# LCD-Micro-PC.net
KiCad netlist of a schematic drawn in EAGLE
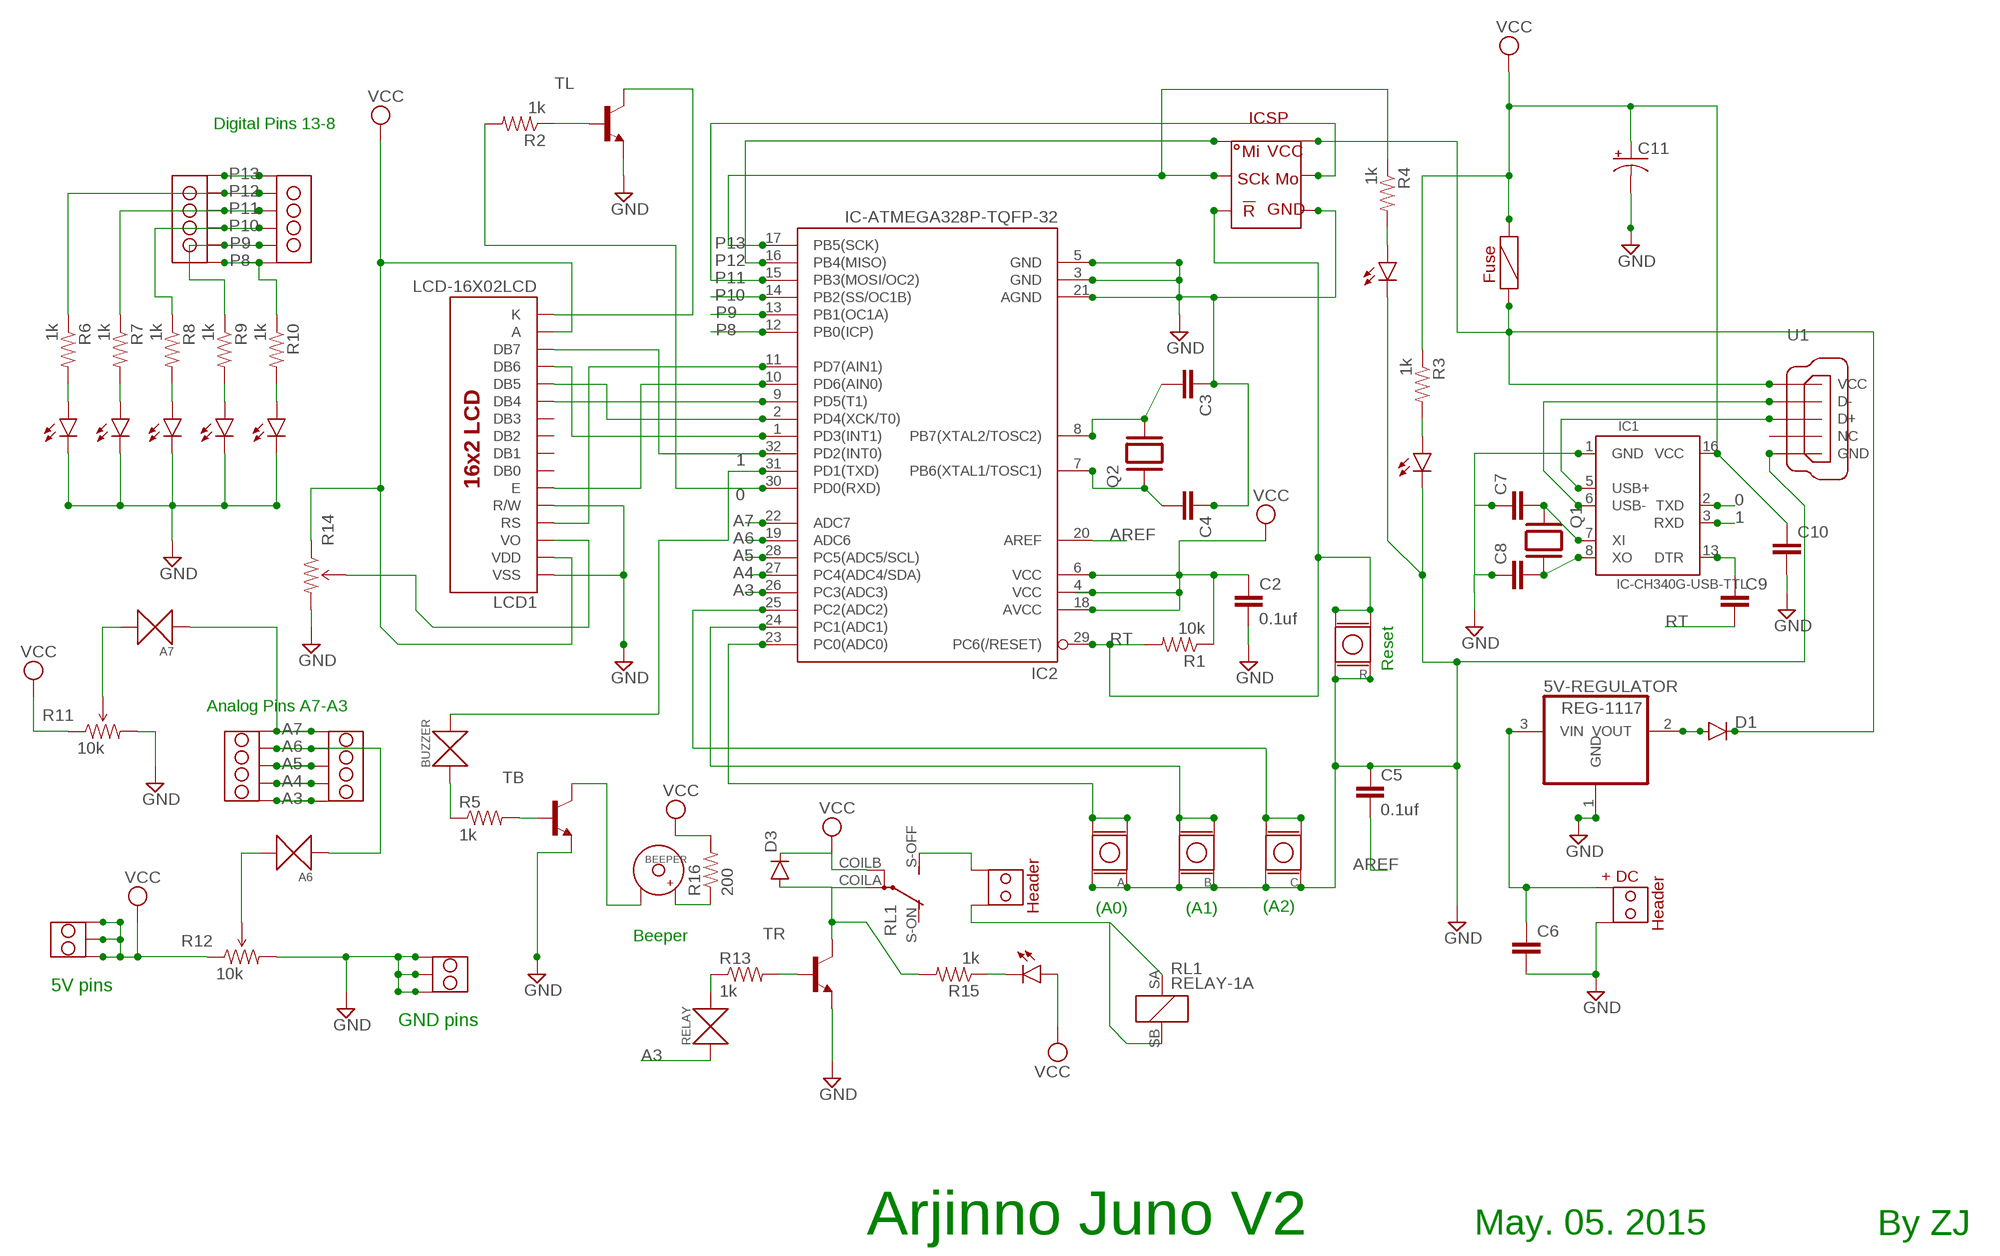
[diagram p0: schematic, sheet 1]

(export (version "E")
  (design (tool "Eeschema 10.0.6"))
  (components
    (comp (ref "5V-REGULATOR")
      (value "REG-1117")
      (footprint "eagle-import:SOT-223@1")
      (fields (field (name "MPN") "REG1117"))
      (libsource (lib "eagle-import") (part "REG-1117"))
    )
    (comp (ref "A")
      (value "BUTTON-6X6")
      (footprint "eagle-import:BUT-6X6")
      (libsource (lib "eagle-import") (part "BUTTON-6X6"))
    )
    (comp (ref "A6")
      (value "TRACE-0.6MM")
      (footprint "eagle-import:TRACE")
      (libsource (lib "eagle-import") (part "TRACE-0.6MM"))
    )
    (comp (ref "A7")
      (value "TRACE-0.6MM")
      (footprint "eagle-import:TRACE")
      (libsource (lib "eagle-import") (part "TRACE-0.6MM"))
    )
    (comp (ref "B")
      (value "BUTTON-6X6")
      (footprint "eagle-import:BUT-6X6")
      (libsource (lib "eagle-import") (part "BUTTON-6X6"))
    )
    (comp (ref "BEEPER")
      (value "BUZZER-12MM")
      (footprint "eagle-import:BUZ-12MM")
      (libsource (lib "eagle-import") (part "BUZZER-12MM"))
    )
    (comp (ref "BUZZER")
      (value "TRACE-0.6MM")
      (footprint "eagle-import:TRACE")
      (libsource (lib "eagle-import") (part "TRACE-0.6MM"))
    )
    (comp (ref "C")
      (value "BUTTON-6X6")
      (footprint "eagle-import:BUT-6X6")
      (libsource (lib "eagle-import") (part "BUTTON-6X6"))
    )
    (comp (ref "C2")
      (value "0.1uf")
      (footprint "eagle-import:0805")
      (libsource (lib "eagle-import") (part "CAP-0805"))
    )
    (comp (ref "C3")
      (value "CAP-0805")
      (footprint "eagle-import:0805")
      (libsource (lib "eagle-import") (part "CAP-0805"))
    )
    (comp (ref "C4")
      (value "CAP-0805")
      (footprint "eagle-import:0805")
      (libsource (lib "eagle-import") (part "CAP-0805"))
    )
    (comp (ref "C5")
      (value "0.1uf")
      (footprint "eagle-import:0805")
      (libsource (lib "eagle-import") (part "CAP-0805"))
    )
    (comp (ref "C6")
      (value "CAP-0805")
      (footprint "eagle-import:0805")
      (libsource (lib "eagle-import") (part "CAP-0805"))
    )
    (comp (ref "C7")
      (value "CAP-SMD-0805")
      (footprint "eagle-import:0805")
      (libsource (lib "eagle-import") (part "CAP-SMD-0805"))
    )
    (comp (ref "C8")
      (value "CAP-SMD-0805")
      (footprint "eagle-import:0805")
      (libsource (lib "eagle-import") (part "CAP-SMD-0805"))
    )
    (comp (ref "C9")
      (value "CAP-SMD-0805")
      (footprint "eagle-import:0805")
      (libsource (lib "eagle-import") (part "CAP-SMD-0805"))
    )
    (comp (ref "C10")
      (value "CAP-SMD-0805")
      (footprint "eagle-import:0805")
      (libsource (lib "eagle-import") (part "CAP-SMD-0805"))
    )
    (comp (ref "C11")
      (value "CAP-POL-6MM-SMD")
      (footprint "eagle-import:CAP-POL-6.3X7.7MM")
      (libsource (lib "eagle-import") (part "CAP-POL-6MM-SMD"))
    )
    (comp (ref "D1")
      (value "DIODE-SMA-4MM")
      (footprint "eagle-import:DIODE-SMA")
      (libsource (lib "eagle-import") (part "DIODE-SMA-4MM"))
    )
    (comp (ref "D3")
      (value "DIODE-SOD-1206")
      (footprint "eagle-import:SOD-1206")
      (libsource (lib "eagle-import") (part "DIODE-SOD-1206"))
    )
    (comp (ref "FUSE")
      (value "FUSE")
      (footprint "eagle-import:0805")
      (libsource (lib "eagle-import") (part "FUSE"))
    )
    (comp (ref "GND")
      (value "HEADER-3P")
      (footprint "eagle-import:HEADER-3P")
      (libsource (lib "eagle-import") (part "HEADER-3P"))
    )
    (comp (ref "H1")
      (value "HEADER-2P")
      (footprint "eagle-import:HEADER-2P")
      (libsource (lib "eagle-import") (part "HEADER-2P"))
    )
    (comp (ref "IC1")
      (value "IC-CH340G-USB-TTL")
      (footprint "eagle-import:SOP-16")
      (libsource (lib "eagle-import") (part "IC-CH340G-USB-TTL"))
    )
    (comp (ref "IC2")
      (value "IC-ATMEGA328P-TQFP-32")
      (footprint "eagle-import:TQFP32-08MM")
      (libsource (lib "eagle-import") (part "IC-ATMEGA328P-TQFP-32"))
    )
    (comp (ref "LCD1")
      (value "LCD-16X02LCD")
      (footprint "eagle-import:LCD-1602")
      (libsource (lib "eagle-import") (part "LCD-16X02LCD"))
    )
    (comp (ref "LED1")
      (value "LED-0805")
      (footprint "eagle-import:LED-0805")
      (libsource (lib "eagle-import") (part "LED-0805"))
    )
    (comp (ref "LED3")
      (value "LED-0805")
      (footprint "eagle-import:LED-0805")
      (libsource (lib "eagle-import") (part "LED-0805"))
    )
    (comp (ref "LED4")
      (value "LED-0805")
      (footprint "eagle-import:LED-0805")
      (libsource (lib "eagle-import") (part "LED-0805"))
    )
    (comp (ref "LED6")
      (value "LED-0805")
      (footprint "eagle-import:LED-0805")
      (libsource (lib "eagle-import") (part "LED-0805"))
    )
    (comp (ref "LED7")
      (value "LED-0805")
      (footprint "eagle-import:LED-0805")
      (libsource (lib "eagle-import") (part "LED-0805"))
    )
    (comp (ref "LED8")
      (value "LED-0805")
      (footprint "eagle-import:LED-0805")
      (libsource (lib "eagle-import") (part "LED-0805"))
    )
    (comp (ref "LED9")
      (value "LED-0805")
      (footprint "eagle-import:LED-0805")
      (libsource (lib "eagle-import") (part "LED-0805"))
    )
    (comp (ref "LED10")
      (value "LED-0805")
      (footprint "eagle-import:LED-0805")
      (libsource (lib "eagle-import") (part "LED-0805"))
    )
    (comp (ref "Q1")
      (value "CRYSTAL-5032")
      (footprint "eagle-import:CRYSTAL-5032")
      (libsource (lib "eagle-import") (part "CRYSTAL-5032"))
    )
    (comp (ref "Q2")
      (value "CRYSTAL-5032")
      (footprint "eagle-import:CRYSTAL-5032")
      (libsource (lib "eagle-import") (part "CRYSTAL-5032"))
    )
    (comp (ref "R")
      (value "BUTTON-4X4-SMD")
      (footprint "eagle-import:BUT-SMD-4X4")
      (libsource (lib "eagle-import") (part "BUTTON-4X4-SMD"))
    )
    (comp (ref "R1")
      (value "10k")
      (footprint "eagle-import:0805")
      (libsource (lib "eagle-import") (part "RES-0805"))
    )
    (comp (ref "R2")
      (value "1k")
      (footprint "eagle-import:0805")
      (libsource (lib "eagle-import") (part "RES-0805"))
    )
    (comp (ref "R3")
      (value "1k")
      (footprint "eagle-import:0805")
      (libsource (lib "eagle-import") (part "RES-0805"))
    )
    (comp (ref "R4")
      (value "1k")
      (footprint "eagle-import:0805")
      (libsource (lib "eagle-import") (part "RES-0805"))
    )
    (comp (ref "R5")
      (value "1k")
      (footprint "eagle-import:0805")
      (libsource (lib "eagle-import") (part "RES-0805"))
    )
    (comp (ref "R6")
      (value "1k")
      (footprint "eagle-import:0805")
      (libsource (lib "eagle-import") (part "RES-0805"))
    )
    (comp (ref "R7")
      (value "1k")
      (footprint "eagle-import:0805")
      (libsource (lib "eagle-import") (part "RES-0805"))
    )
    (comp (ref "R8")
      (value "1k")
      (footprint "eagle-import:0805")
      (libsource (lib "eagle-import") (part "RES-0805"))
    )
    (comp (ref "R9")
      (value "1k")
      (footprint "eagle-import:0805")
      (libsource (lib "eagle-import") (part "RES-0805"))
    )
    (comp (ref "R10")
      (value "1k")
      (footprint "eagle-import:0805")
      (libsource (lib "eagle-import") (part "RES-0805"))
    )
    (comp (ref "R11")
      (value "10k")
      (footprint "eagle-import:POT-5X5MM@1")
      (libsource (lib "eagle-import") (part "POT-6MM-0505"))
    )
    (comp (ref "R12")
      (value "10k")
      (footprint "eagle-import:POT-10X10MM@1")
      (libsource (lib "eagle-import") (part "POT-10MM"))
    )
    (comp (ref "R13")
      (value "1k")
      (footprint "eagle-import:0805")
      (libsource (lib "eagle-import") (part "RES-0805"))
    )
    (comp (ref "R14")
      (value "POTENTIOMETER-3MM-SMD")
      (footprint "eagle-import:POT-3MM-SMD")
      (libsource (lib "eagle-import") (part "POTENTIOMETER-3MM-SMD"))
    )
    (comp (ref "R15")
      (value "1k")
      (footprint "eagle-import:0805")
      (libsource (lib "eagle-import") (part "RES-0805"))
    )
    (comp (ref "R16")
      (value "200")
      (footprint "eagle-import:0805")
      (libsource (lib "eagle-import") (part "RES-0805"))
    )
    (comp (ref "RELAY")
      (value "TRACE-0.6MM")
      (footprint "eagle-import:TRACE")
      (libsource (lib "eagle-import") (part "TRACE-0.6MM"))
    )
    (comp (ref "RL1")
      (value "RELAY-1A")
      (footprint "eagle-import:REL-G5V1")
      (libsource (lib "eagle-import") (part "RELAY-1A"))
    )
    (comp (ref "TB")
      (value "NPN-S8050-J3Y-0.3W")
      (footprint "eagle-import:SOT-23")
      (libsource (lib "eagle-import") (part "NPN-S8050-J3Y-0.3W"))
    )
    (comp (ref "TL")
      (value "NPN-S8050-J3Y-0.3W")
      (footprint "eagle-import:SOT-23")
      (libsource (lib "eagle-import") (part "NPN-S8050-J3Y-0.3W"))
    )
    (comp (ref "TR")
      (value "NPN-S8050-J3Y-0.3W")
      (footprint "eagle-import:SOT-23")
      (libsource (lib "eagle-import") (part "NPN-S8050-J3Y-0.3W"))
    )
    (comp (ref "U$1")
      (value "ISCP-6PINS")
      (footprint "eagle-import:ISCP")
      (libsource (lib "eagle-import") (part "ISCP-6PINS"))
    )
    (comp (ref "U$2")
      (value "HEADER-2P-DC")
      (footprint "eagle-import:HEADER-2P-DC")
      (libsource (lib "eagle-import") (part "HEADER-2P-DC"))
    )
    (comp (ref "U$9")
      (value "HEADER-5P")
      (footprint "eagle-import:HEADER-5P")
      (libsource (lib "eagle-import") (part "HEADER-5P"))
    )
    (comp (ref "U$10")
      (value "HEADER-6P")
      (footprint "eagle-import:HEADER-6P")
      (libsource (lib "eagle-import") (part "HEADER-6P"))
    )
    (comp (ref "U$11")
      (value "HEADER-6P")
      (footprint "eagle-import:HEADER-6P")
      (libsource (lib "eagle-import") (part "HEADER-6P"))
    )
    (comp (ref "U$12")
      (value "HEADER-5P")
      (footprint "eagle-import:HEADER-5P")
      (libsource (lib "eagle-import") (part "HEADER-5P"))
    )
    (comp (ref "U1")
      (value "USB-MINI")
      (footprint "eagle-import:USB-MINI")
      (libsource (lib "eagle-import") (part "USB-MINI"))
    )
    (comp (ref "VCC")
      (value "HEADER-3P")
      (footprint "eagle-import:HEADER-3P")
      (libsource (lib "eagle-import") (part "HEADER-3P"))
    )
  )
  (nets
    (net (code "1") (name "/0") (class "Default")
      (node (ref "IC1") (pin "2") (pinfunction "TXD_2") (pintype "bidirectional"))
      (node (ref "IC2") (pin "30") (pinfunction "PD0(RXD)_30") (pintype "bidirectional"))
      (node (ref "R2") (pin "2") (pinfunction "2_2") (pintype "passive"))
    )
    (net (code "2") (name "/1") (class "Default")
      (node (ref "BUZZER") (pin "P$2") (pinfunction "P$2_P$2") (pintype "passive"))
      (node (ref "IC1") (pin "3") (pinfunction "RXD_3") (pintype "bidirectional"))
      (node (ref "IC2") (pin "31") (pinfunction "PD1(TXD)_31") (pintype "bidirectional"))
    )
    (net (code "3") (name "/A3") (class "Default")
      (node (ref "IC2") (pin "26") (pinfunction "PC3(ADC3)_26") (pintype "bidirectional"))
      (node (ref "RELAY") (pin "P$1") (pinfunction "P$1_P$1") (pintype "passive"))
      (node (ref "U$12") (pin "P$1") (pinfunction "P$1_P$1") (pintype "bidirectional"))
      (node (ref "U$9") (pin "P$5") (pinfunction "P$5_P$5") (pintype "bidirectional"))
    )
    (net (code "4") (name "/A4") (class "Default")
      (node (ref "IC2") (pin "27") (pinfunction "PC4(ADC4/SDA)_27") (pintype "bidirectional"))
      (node (ref "U$12") (pin "P$2") (pinfunction "P$2_P$2") (pintype "bidirectional"))
      (node (ref "U$9") (pin "P$4") (pinfunction "P$4_P$4") (pintype "bidirectional"))
    )
    (net (code "5") (name "/A5") (class "Default")
      (node (ref "IC2") (pin "28") (pinfunction "PC5(ADC5/SCL)_28") (pintype "bidirectional"))
      (node (ref "U$12") (pin "P$3") (pinfunction "P$3_P$3") (pintype "bidirectional"))
      (node (ref "U$9") (pin "P$3") (pinfunction "P$3_P$3") (pintype "bidirectional"))
    )
    (net (code "6") (name "/A6") (class "Default")
      (node (ref "A6") (pin "P$1") (pinfunction "P$1_P$1") (pintype "passive"))
      (node (ref "IC2") (pin "19") (pinfunction "ADC6_19") (pintype "bidirectional"))
      (node (ref "U$12") (pin "P$4") (pinfunction "P$4_P$4") (pintype "bidirectional"))
      (node (ref "U$9") (pin "P$2") (pinfunction "P$2_P$2") (pintype "bidirectional"))
    )
    (net (code "7") (name "/A7") (class "Default")
      (node (ref "A7") (pin "P$1") (pinfunction "P$1_P$1") (pintype "passive"))
      (node (ref "IC2") (pin "22") (pinfunction "ADC7_22") (pintype "bidirectional"))
      (node (ref "U$12") (pin "P$5") (pinfunction "P$5_P$5") (pintype "bidirectional"))
      (node (ref "U$9") (pin "P$1") (pinfunction "P$1_P$1") (pintype "bidirectional"))
    )
    (net (code "8") (name "/AREF") (class "Default")
      (node (ref "C5") (pin "2") (pinfunction "2_2") (pintype "passive"))
      (node (ref "IC2") (pin "20") (pinfunction "AREF_20") (pintype "bidirectional"))
    )
    (net (code "9") (name "/P8") (class "Default")
      (node (ref "IC2") (pin "12") (pinfunction "PB0(ICP)_12") (pintype "bidirectional"))
      (node (ref "R10") (pin "1") (pinfunction "1_1") (pintype "passive"))
      (node (ref "U$10") (pin "P$6") (pinfunction "P$6_P$6") (pintype "bidirectional"))
      (node (ref "U$11") (pin "P$1") (pinfunction "P$1_P$1") (pintype "bidirectional"))
    )
    (net (code "10") (name "/P9") (class "Default")
      (node (ref "IC2") (pin "13") (pinfunction "PB1(OC1A)_13") (pintype "bidirectional"))
      (node (ref "R9") (pin "1") (pinfunction "1_1") (pintype "passive"))
      (node (ref "U$10") (pin "P$5") (pinfunction "P$5_P$5") (pintype "bidirectional"))
      (node (ref "U$11") (pin "P$2") (pinfunction "P$2_P$2") (pintype "bidirectional"))
    )
    (net (code "11") (name "/P10") (class "Default")
      (node (ref "IC2") (pin "14") (pinfunction "PB2(SS/OC1B)_14") (pintype "bidirectional"))
      (node (ref "R8") (pin "1") (pinfunction "1_1") (pintype "passive"))
      (node (ref "U$10") (pin "P$4") (pinfunction "P$4_P$4") (pintype "bidirectional"))
      (node (ref "U$11") (pin "P$3") (pinfunction "P$3_P$3") (pintype "bidirectional"))
    )
    (net (code "12") (name "/P11") (class "Default")
      (node (ref "IC2") (pin "15") (pinfunction "PB3(MOSI/OC2)_15") (pintype "bidirectional"))
      (node (ref "R7") (pin "1") (pinfunction "1_1") (pintype "passive"))
      (node (ref "U$1") (pin "P$5") (pinfunction "P$5_P$5") (pintype "bidirectional"))
      (node (ref "U$10") (pin "P$3") (pinfunction "P$3_P$3") (pintype "bidirectional"))
      (node (ref "U$11") (pin "P$4") (pinfunction "P$4_P$4") (pintype "bidirectional"))
    )
    (net (code "13") (name "/P12") (class "Default")
      (node (ref "IC2") (pin "16") (pinfunction "PB4(MISO)_16") (pintype "bidirectional"))
      (node (ref "R6") (pin "1") (pinfunction "1_1") (pintype "passive"))
      (node (ref "U$1") (pin "P$1") (pinfunction "P$1_P$1") (pintype "bidirectional"))
      (node (ref "U$10") (pin "P$2") (pinfunction "P$2_P$2") (pintype "bidirectional"))
      (node (ref "U$11") (pin "P$5") (pinfunction "P$5_P$5") (pintype "bidirectional"))
    )
    (net (code "14") (name "/P13") (class "Default")
      (node (ref "IC2") (pin "17") (pinfunction "PB5(SCK)_17") (pintype "bidirectional"))
      (node (ref "R4") (pin "1") (pinfunction "1_1") (pintype "passive"))
      (node (ref "U$1") (pin "P$2") (pinfunction "P$2_P$2") (pintype "bidirectional"))
      (node (ref "U$10") (pin "P$1") (pinfunction "P$1_P$1") (pintype "bidirectional"))
      (node (ref "U$11") (pin "P$6") (pinfunction "P$6_P$6") (pintype "bidirectional"))
    )
    (net (code "15") (name "/RT") (class "Default")
      (node (ref "C9") (pin "2") (pinfunction "2_2") (pintype "passive"))
      (node (ref "IC2") (pin "29") (pinfunction "PC6(/RESET)_29") (pintype "bidirectional"))
      (node (ref "R") (pin "A0") (pinfunction "A0_A0") (pintype "bidirectional"))
      (node (ref "R") (pin "A1") (pinfunction "A1_A1") (pintype "bidirectional"))
      (node (ref "R1") (pin "2") (pinfunction "2_2") (pintype "passive"))
      (node (ref "U$1") (pin "P$3") (pinfunction "P$3_P$3") (pintype "bidirectional"))
    )
    (net (code "16") (name "GND") (class "Default")
      (node (ref "5V-REGULATOR") (pin "1") (pinfunction "GND_1") (pintype "power_in"))
      (node (ref "A") (pin "B0") (pinfunction "B0_B0") (pintype "bidirectional"))
      (node (ref "A") (pin "B1") (pinfunction "B1_B1") (pintype "bidirectional"))
      (node (ref "B") (pin "B0") (pinfunction "B0_B0") (pintype "bidirectional"))
      (node (ref "B") (pin "B1") (pinfunction "B1_B1") (pintype "bidirectional"))
      (node (ref "C") (pin "B0") (pinfunction "B0_B0") (pintype "bidirectional"))
      (node (ref "C") (pin "B1") (pinfunction "B1_B1") (pintype "bidirectional"))
      (node (ref "C10") (pin "2") (pinfunction "2_2") (pintype "passive"))
      (node (ref "C11") (pin "-") (pinfunction "-_-") (pintype "passive"))
      (node (ref "C2") (pin "2") (pinfunction "2_2") (pintype "passive"))
      (node (ref "C3") (pin "1") (pinfunction "1_1") (pintype "passive"))
      (node (ref "C4") (pin "1") (pinfunction "1_1") (pintype "passive"))
      (node (ref "C5") (pin "1") (pinfunction "1_1") (pintype "passive"))
      (node (ref "C6") (pin "2") (pinfunction "2_2") (pintype "passive"))
      (node (ref "C7") (pin "1") (pinfunction "1_1") (pintype "passive"))
      (node (ref "C8") (pin "1") (pinfunction "1_1") (pintype "passive"))
      (node (ref "GND") (pin "P$1") (pinfunction "P$1_P$1") (pintype "bidirectional"))
      (node (ref "GND") (pin "P$2") (pinfunction "P$2_P$2") (pintype "bidirectional"))
      (node (ref "GND") (pin "P$3") (pinfunction "P$3_P$3") (pintype "bidirectional"))
      (node (ref "IC1") (pin "1") (pinfunction "GND_1") (pintype "bidirectional"))
      (node (ref "IC2") (pin "21") (pinfunction "AGND_21") (pintype "bidirectional"))
      (node (ref "IC2") (pin "3") (pinfunction "GND_3") (pintype "bidirectional"))
      (node (ref "IC2") (pin "5") (pinfunction "GND_5") (pintype "bidirectional"))
      (node (ref "LCD1") (pin "1") (pinfunction "VSS_1") (pintype "power_in"))
      (node (ref "LCD1") (pin "5") (pinfunction "R/W_5") (pintype "input"))
      (node (ref "LED10") (pin "C") (pinfunction "C_C") (pintype "passive"))
      (node (ref "LED3") (pin "C") (pinfunction "C_C") (pintype "passive"))
      (node (ref "LED4") (pin "C") (pinfunction "C_C") (pintype "passive"))
      (node (ref "LED6") (pin "C") (pinfunction "C_C") (pintype "passive"))
      (node (ref "LED7") (pin "C") (pinfunction "C_C") (pintype "passive"))
      (node (ref "LED8") (pin "C") (pinfunction "C_C") (pintype "passive"))
      (node (ref "LED9") (pin "C") (pinfunction "C_C") (pintype "passive"))
      (node (ref "R") (pin "B1") (pinfunction "B0_B1") (pintype "bidirectional"))
      (node (ref "R") (pin "B2") (pinfunction "B1_B2") (pintype "bidirectional"))
      (node (ref "R11") (pin "3") (pinfunction "CW_3") (pintype "passive"))
      (node (ref "R12") (pin "3") (pinfunction "CW_3") (pintype "passive"))
      (node (ref "R14") (pin "3") (pinfunction "CW_3") (pintype "passive"))
      (node (ref "TB") (pin "2") (pinfunction "E_2") (pintype "passive"))
      (node (ref "TL") (pin "2") (pinfunction "E_2") (pintype "passive"))
      (node (ref "TR") (pin "2") (pinfunction "E_2") (pintype "passive"))
      (node (ref "U$1") (pin "P$4") (pinfunction "P$4_P$4") (pintype "bidirectional"))
      (node (ref "U$2") (pin "-") (pinfunction "-_-") (pintype "bidirectional"))
      (node (ref "U1") (pin "5") (pinfunction "GND_5") (pintype "passive"))
    )
    (net (code "17") (name "Net-(5V-REGULATOR-VIN)") (class "Default")
      (node (ref "5V-REGULATOR") (pin "3") (pinfunction "VIN_3") (pintype "input"))
      (node (ref "C6") (pin "1") (pinfunction "1_1") (pintype "passive"))
      (node (ref "U$2") (pin "+") (pinfunction "+_+") (pintype "bidirectional"))
    )
    (net (code "18") (name "Net-(5V-REGULATOR-VOUT)") (class "Default")
      (node (ref "5V-REGULATOR") (pin "2") (pinfunction "VOUT_2") (pintype "output"))
      (node (ref "D1") (pin "A") (pinfunction "A_A") (pintype "passive"))
    )
    (net (code "19") (name "Net-(BEEPER-P$1)") (class "Default")
      (node (ref "BEEPER") (pin "-") (pinfunction "P$1_-") (pintype "bidirectional"))
      (node (ref "TB") (pin "3") (pinfunction "C_3") (pintype "passive"))
    )
    (net (code "20") (name "Net-(BEEPER-P$2)") (class "Default")
      (node (ref "BEEPER") (pin "+") (pinfunction "P$2_+") (pintype "bidirectional"))
      (node (ref "R16") (pin "1") (pinfunction "1_1") (pintype "passive"))
    )
    (net (code "21") (name "Net-(BUZZER-PadP$1)") (class "Default")
      (node (ref "BUZZER") (pin "P$1") (pinfunction "P$1_P$1") (pintype "passive"))
      (node (ref "R5") (pin "1") (pinfunction "1_1") (pintype "passive"))
    )
    (net (code "22") (name "Net-(FUSE-P$1)") (class "Default")
      (node (ref "D1") (pin "C") (pinfunction "C_C") (pintype "passive"))
      (node (ref "FUSE") (pin "1") (pinfunction "P$1_1") (pintype "bidirectional"))
      (node (ref "U$1") (pin "P$6") (pinfunction "P$6_P$6") (pintype "bidirectional"))
      (node (ref "U1") (pin "1") (pinfunction "VCC_1") (pintype "passive"))
    )
    (net (code "23") (name "Net-(H1-+)") (class "Default")
      (node (ref "H1") (pin "P$1") (pinfunction "+_P$1") (pintype "bidirectional"))
      (node (ref "RL1") (pin "S-OFF") (pinfunction "SW_S-OFF") (pintype "passive"))
    )
    (net (code "24") (name "Net-(H1--)") (class "Default")
      (node (ref "H1") (pin "P$2") (pinfunction "-_P$2") (pintype "bidirectional"))
      (node (ref "RL1") (pin "SA") (pinfunction "1_SA") (pintype "passive"))
      (node (ref "RL1") (pin "SB") (pinfunction "2_SB") (pintype "passive"))
    )
    (net (code "25") (name "Net-(IC1-DTR)") (class "Default")
      (node (ref "C9") (pin "1") (pinfunction "1_1") (pintype "passive"))
      (node (ref "IC1") (pin "13") (pinfunction "DTR_13") (pintype "bidirectional"))
    )
    (net (code "26") (name "Net-(IC1-USB+)") (class "Default")
      (node (ref "IC1") (pin "5") (pinfunction "USB+_5") (pintype "bidirectional"))
      (node (ref "U1") (pin "3") (pinfunction "D+_3") (pintype "passive"))
    )
    (net (code "27") (name "Net-(IC1-USB-)") (class "Default")
      (node (ref "IC1") (pin "6") (pinfunction "USB-_6") (pintype "bidirectional"))
      (node (ref "U1") (pin "2") (pinfunction "D-_2") (pintype "passive"))
    )
    (net (code "28") (name "Net-(IC1-XI)") (class "Default")
      (node (ref "C7") (pin "2") (pinfunction "2_2") (pintype "passive"))
      (node (ref "IC1") (pin "7") (pinfunction "XI_7") (pintype "bidirectional"))
      (node (ref "Q1") (pin "1") (pinfunction "1_1") (pintype "passive"))
    )
    (net (code "29") (name "Net-(IC1-XO)") (class "Default")
      (node (ref "C8") (pin "2") (pinfunction "2_2") (pintype "passive"))
      (node (ref "IC1") (pin "8") (pinfunction "XO_8") (pintype "bidirectional"))
      (node (ref "Q1") (pin "2") (pinfunction "2_2") (pintype "passive"))
    )
    (net (code "30") (name "Net-(IC2-PB6(XTAL1{slash}TOSC1))") (class "Default")
      (node (ref "C4") (pin "2") (pinfunction "2_2") (pintype "passive"))
      (node (ref "IC2") (pin "7") (pinfunction "PB6(XTAL1/TOSC1)_7") (pintype "bidirectional"))
      (node (ref "Q2") (pin "1") (pinfunction "1_1") (pintype "passive"))
    )
    (net (code "31") (name "Net-(IC2-PB7(XTAL2{slash}TOSC2))") (class "Default")
      (node (ref "C3") (pin "2") (pinfunction "2_2") (pintype "passive"))
      (node (ref "IC2") (pin "8") (pinfunction "PB7(XTAL2/TOSC2)_8") (pintype "bidirectional"))
      (node (ref "Q2") (pin "2") (pinfunction "2_2") (pintype "passive"))
    )
    (net (code "32") (name "Net-(IC2-PC0(ADC0))") (class "Default")
      (node (ref "A") (pin "A0") (pinfunction "A0_A0") (pintype "bidirectional"))
      (node (ref "A") (pin "A1") (pinfunction "A1_A1") (pintype "bidirectional"))
      (node (ref "IC2") (pin "23") (pinfunction "PC0(ADC0)_23") (pintype "bidirectional"))
    )
    (net (code "33") (name "Net-(IC2-PC1(ADC1))") (class "Default")
      (node (ref "B") (pin "A0") (pinfunction "A0_A0") (pintype "bidirectional"))
      (node (ref "B") (pin "A1") (pinfunction "A1_A1") (pintype "bidirectional"))
      (node (ref "IC2") (pin "24") (pinfunction "PC1(ADC1)_24") (pintype "bidirectional"))
    )
    (net (code "34") (name "Net-(IC2-PC2(ADC2))") (class "Default")
      (node (ref "C") (pin "A0") (pinfunction "A0_A0") (pintype "bidirectional"))
      (node (ref "C") (pin "A1") (pinfunction "A1_A1") (pintype "bidirectional"))
      (node (ref "IC2") (pin "25") (pinfunction "PC2(ADC2)_25") (pintype "bidirectional"))
    )
    (net (code "35") (name "Net-(IC2-PD2(INT0))") (class "Default")
      (node (ref "IC2") (pin "32") (pinfunction "PD2(INT0)_32") (pintype "bidirectional"))
      (node (ref "LCD1") (pin "14") (pinfunction "DB7_14") (pintype "bidirectional"))
    )
    (net (code "36") (name "Net-(IC2-PD3(INT1))") (class "Default")
      (node (ref "IC2") (pin "1") (pinfunction "PD3(INT1)_1") (pintype "bidirectional"))
      (node (ref "LCD1") (pin "13") (pinfunction "DB6_13") (pintype "bidirectional"))
    )
    (net (code "37") (name "Net-(IC2-PD4(XCK{slash}T0))") (class "Default")
      (node (ref "IC2") (pin "2") (pinfunction "PD4(XCK/T0)_2") (pintype "bidirectional"))
      (node (ref "LCD1") (pin "12") (pinfunction "DB5_12") (pintype "bidirectional"))
    )
    (net (code "38") (name "Net-(IC2-PD5(T1))") (class "Default")
      (node (ref "IC2") (pin "9") (pinfunction "PD5(T1)_9") (pintype "bidirectional"))
      (node (ref "LCD1") (pin "11") (pinfunction "DB4_11") (pintype "bidirectional"))
    )
    (net (code "39") (name "Net-(IC2-PD6(AIN0))") (class "Default")
      (node (ref "IC2") (pin "10") (pinfunction "PD6(AIN0)_10") (pintype "bidirectional"))
      (node (ref "LCD1") (pin "6") (pinfunction "E_6") (pintype "input"))
    )
    (net (code "40") (name "Net-(IC2-PD7(AIN1))") (class "Default")
      (node (ref "IC2") (pin "11") (pinfunction "PD7(AIN1)_11") (pintype "bidirectional"))
      (node (ref "LCD1") (pin "4") (pinfunction "RS_4") (pintype "input"))
    )
    (net (code "41") (name "Net-(LCD1-K)") (class "Default")
      (node (ref "LCD1") (pin "16") (pinfunction "K_16") (pintype "power_in"))
      (node (ref "TL") (pin "3") (pinfunction "C_3") (pintype "passive"))
    )
    (net (code "42") (name "Net-(LCD1-VO)") (class "Default")
      (node (ref "LCD1") (pin "3") (pinfunction "VO_3") (pintype "bidirectional"))
      (node (ref "R14") (pin "2") (pinfunction "WIPER_2") (pintype "passive"))
    )
    (net (code "43") (name "Net-(LED1-PadC)") (class "Default")
      (node (ref "LED1") (pin "C") (pinfunction "C_C") (pintype "passive"))
      (node (ref "R15") (pin "1") (pinfunction "1_1") (pintype "passive"))
    )
    (net (code "44") (name "Net-(LED3-PadA)") (class "Default")
      (node (ref "LED3") (pin "A") (pinfunction "A_A") (pintype "passive"))
      (node (ref "R3") (pin "2") (pinfunction "2_2") (pintype "passive"))
    )
    (net (code "45") (name "Net-(LED4-PadA)") (class "Default")
      (node (ref "LED4") (pin "A") (pinfunction "A_A") (pintype "passive"))
      (node (ref "R4") (pin "2") (pinfunction "2_2") (pintype "passive"))
    )
    (net (code "46") (name "Net-(LED6-PadA)") (class "Default")
      (node (ref "LED6") (pin "A") (pinfunction "A_A") (pintype "passive"))
      (node (ref "R6") (pin "2") (pinfunction "2_2") (pintype "passive"))
    )
    (net (code "47") (name "Net-(LED7-PadA)") (class "Default")
      (node (ref "LED7") (pin "A") (pinfunction "A_A") (pintype "passive"))
      (node (ref "R7") (pin "2") (pinfunction "2_2") (pintype "passive"))
    )
    (net (code "48") (name "Net-(LED8-PadA)") (class "Default")
      (node (ref "LED8") (pin "A") (pinfunction "A_A") (pintype "passive"))
      (node (ref "R8") (pin "2") (pinfunction "2_2") (pintype "passive"))
    )
    (net (code "49") (name "Net-(LED9-PadA)") (class "Default")
      (node (ref "LED9") (pin "A") (pinfunction "A_A") (pintype "passive"))
      (node (ref "R9") (pin "2") (pinfunction "2_2") (pintype "passive"))
    )
    (net (code "50") (name "Net-(LED10-PadA)") (class "Default")
      (node (ref "LED10") (pin "A") (pinfunction "A_A") (pintype "passive"))
      (node (ref "R10") (pin "2") (pinfunction "2_2") (pintype "passive"))
    )
    (net (code "51") (name "Net-(R11-WIPER)") (class "Default")
      (node (ref "A7") (pin "P$2") (pinfunction "P$2_P$2") (pintype "passive"))
      (node (ref "R11") (pin "2") (pinfunction "WIPER_2") (pintype "passive"))
    )
    (net (code "52") (name "Net-(R12-WIPER)") (class "Default")
      (node (ref "A6") (pin "P$2") (pinfunction "P$2_P$2") (pintype "passive"))
      (node (ref "R12") (pin "2") (pinfunction "WIPER_2") (pintype "passive"))
    )
    (net (code "53") (name "Net-(R13-Pad1)") (class "Default")
      (node (ref "R13") (pin "1") (pinfunction "1_1") (pintype "passive"))
      (node (ref "RELAY") (pin "P$2") (pinfunction "P$2_P$2") (pintype "passive"))
    )
    (net (code "54") (name "Net-(TB-B)") (class "Default")
      (node (ref "R5") (pin "2") (pinfunction "2_2") (pintype "passive"))
      (node (ref "TB") (pin "1") (pinfunction "B_1") (pintype "passive"))
    )
    (net (code "55") (name "Net-(TL-B)") (class "Default")
      (node (ref "R2") (pin "1") (pinfunction "1_1") (pintype "passive"))
      (node (ref "TL") (pin "1") (pinfunction "B_1") (pintype "passive"))
    )
    (net (code "56") (name "Net-(TR-B)") (class "Default")
      (node (ref "R13") (pin "2") (pinfunction "2_2") (pintype "passive"))
      (node (ref "TR") (pin "1") (pinfunction "B_1") (pintype "passive"))
    )
    (net (code "57") (name "Net-(TR-C)") (class "Default")
      (node (ref "D3") (pin "A") (pinfunction "A_A") (pintype "passive"))
      (node (ref "R15") (pin "2") (pinfunction "2_2") (pintype "passive"))
      (node (ref "RL1") (pin "COILA") (pinfunction "P_COILA") (pintype "passive"))
      (node (ref "TR") (pin "3") (pinfunction "C_3") (pintype "passive"))
    )
    (net (code "58") (name "VCC") (class "Default")
      (node (ref "C10") (pin "1") (pinfunction "1_1") (pintype "passive"))
      (node (ref "C11") (pin "+") (pinfunction "+_+") (pintype "passive"))
      (node (ref "C2") (pin "1") (pinfunction "1_1") (pintype "passive"))
      (node (ref "D3") (pin "C") (pinfunction "C_C") (pintype "passive"))
      (node (ref "FUSE") (pin "2") (pinfunction "P$2_2") (pintype "bidirectional"))
      (node (ref "IC1") (pin "16") (pinfunction "VCC_16") (pintype "bidirectional"))
      (node (ref "IC2") (pin "18") (pinfunction "AVCC_18") (pintype "bidirectional"))
      (node (ref "IC2") (pin "4") (pinfunction "VCC_4") (pintype "bidirectional"))
      (node (ref "IC2") (pin "6") (pinfunction "VCC_6") (pintype "bidirectional"))
      (node (ref "LCD1") (pin "15") (pinfunction "A_15") (pintype "power_in"))
      (node (ref "LCD1") (pin "2") (pinfunction "VDD_2") (pintype "power_in"))
      (node (ref "LED1") (pin "A") (pinfunction "A_A") (pintype "passive"))
      (node (ref "R1") (pin "1") (pinfunction "1_1") (pintype "passive"))
      (node (ref "R11") (pin "1") (pinfunction "CCW_1") (pintype "passive"))
      (node (ref "R12") (pin "1") (pinfunction "CCW_1") (pintype "passive"))
      (node (ref "R14") (pin "1") (pinfunction "CCW_1") (pintype "passive"))
      (node (ref "R16") (pin "2") (pinfunction "2_2") (pintype "passive"))
      (node (ref "R3") (pin "1") (pinfunction "1_1") (pintype "passive"))
      (node (ref "RL1") (pin "COILB") (pinfunction "P_COILB") (pintype "passive"))
      (node (ref "VCC") (pin "P$1") (pinfunction "P$1_P$1") (pintype "bidirectional"))
      (node (ref "VCC") (pin "P$2") (pinfunction "P$2_P$2") (pintype "bidirectional"))
      (node (ref "VCC") (pin "P$3") (pinfunction "P$3_P$3") (pintype "bidirectional"))
    )
    (net (code "59") (name "unconnected-(LCD1-DB0-Pad7)") (class "Default")
      (node (ref "LCD1") (pin "7") (pinfunction "DB0_7") (pintype "bidirectional"))
    )
    (net (code "60") (name "unconnected-(LCD1-DB1-Pad8)") (class "Default")
      (node (ref "LCD1") (pin "8") (pinfunction "DB1_8") (pintype "bidirectional"))
    )
    (net (code "61") (name "unconnected-(LCD1-DB2-Pad9)") (class "Default")
      (node (ref "LCD1") (pin "9") (pinfunction "DB2_9") (pintype "bidirectional"))
    )
    (net (code "62") (name "unconnected-(LCD1-DB3-Pad10)") (class "Default")
      (node (ref "LCD1") (pin "10") (pinfunction "DB3_10") (pintype "bidirectional"))
    )
    (net (code "63") (name "unconnected-(RL1A-ON-PadS-ON)") (class "Default")
      (node (ref "RL1") (pin "S-ON") (pinfunction "ON_S-ON") (pintype "passive"))
    )
    (net (code "64") (name "unconnected-(U1-NC-Pad4)") (class "Default")
      (node (ref "U1") (pin "4") (pinfunction "NC_4") (pintype "passive"))
    )
  )
)
